# DVT-Volga-V2.net
KiCad netlist of a schematic drawn in Altium Designer
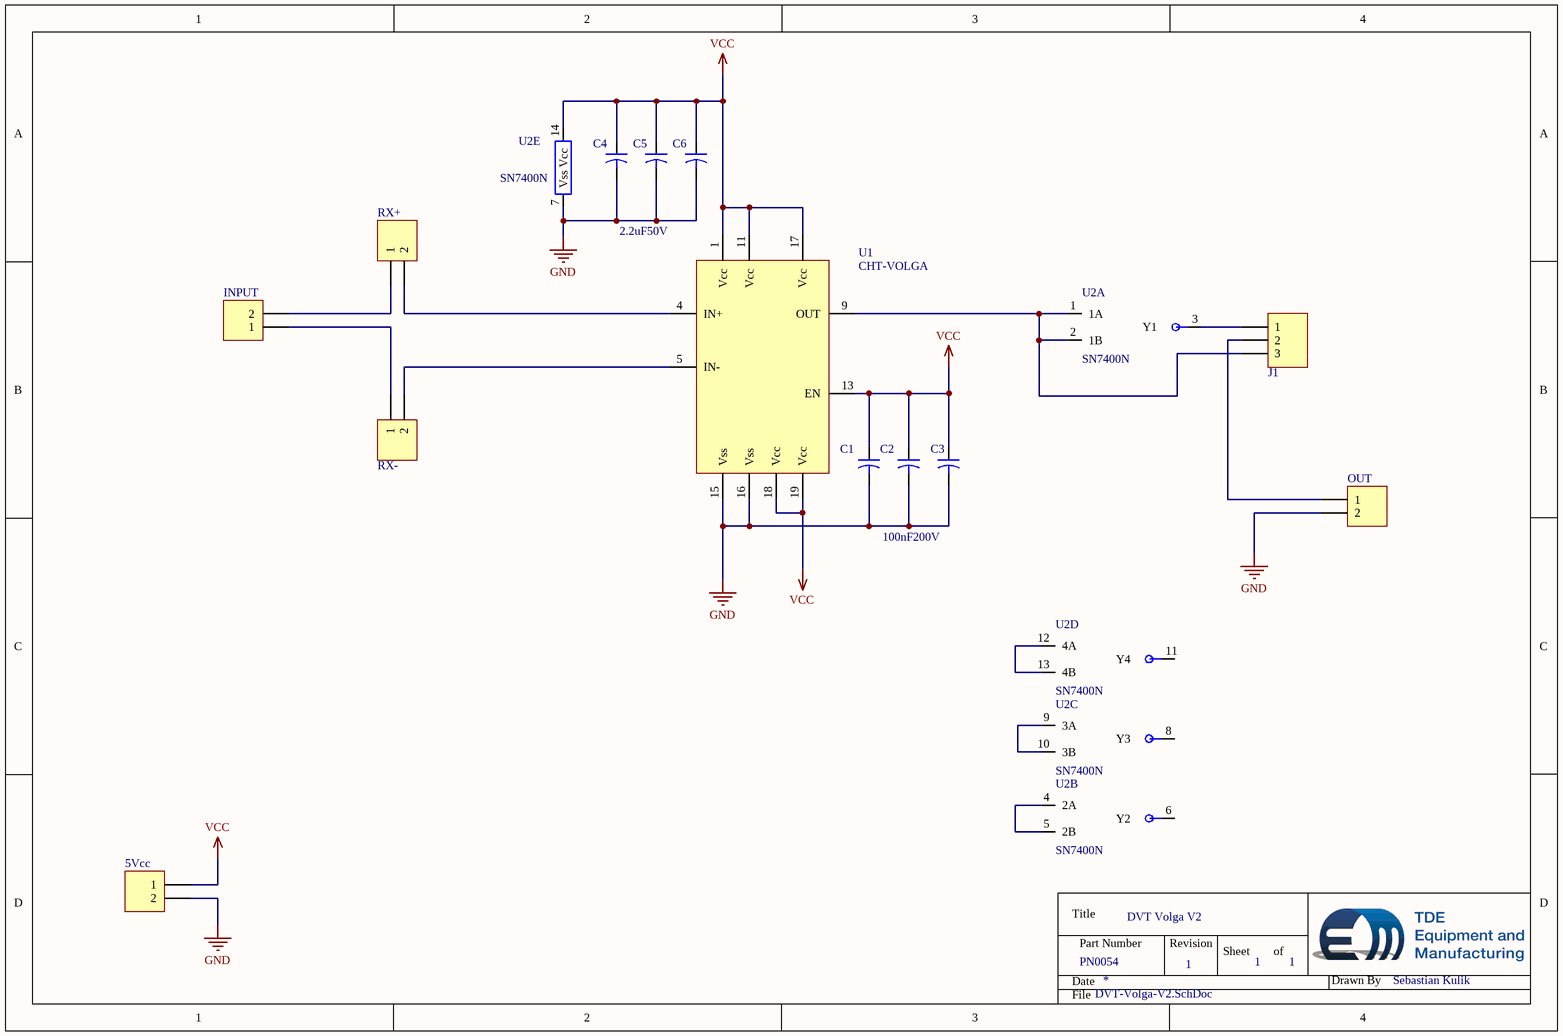
[diagram p0: DVT-Volga-V2.SchDoc]

(export (version "E")
  (design (tool "Eeschema 10.0.6"))
  (components
    (comp (ref "5Vcc")
      (value "PHOENIX_1715721")
      (footprint "Phoenix-2-5_08")
      (description "Phoenix, 2 pol, 5.08mm, 22A, 715721")
      (fields (field (name "MANUFACTURER") "Phoenix") (field (name "PUBLISHER") "Sebastian Kulik"))
      (libsource (lib "Connectors") (part "2Pol_1715721"))
    )
    (comp (ref "C1")
      (value "100nF200V")
      (footprint "Dummy-10mm")
      (description "Capacitor-Dummy-THT")
      (fields (field (name "PUBLISHER") "Sebastian Kulik"))
      (libsource (lib "Capacitors") (part "Capacitor-Dummy-THT"))
    )
    (comp (ref "C2")
      (value "Capacitor-Dummy-THT")
      (footprint "Dummy-10mm")
      (fields (field (name "PUBLISHER") "Sebastian Kulik"))
      (libsource (lib "Capacitors") (part "Capacitor-Dummy-THT"))
    )
    (comp (ref "C3")
      (value "Capacitor-Dummy-THT")
      (footprint "Dummy-10mm")
      (fields (field (name "PUBLISHER") "Sebastian Kulik"))
      (libsource (lib "Capacitors") (part "Capacitor-Dummy-THT"))
    )
    (comp (ref "C4")
      (value "Capacitor-Dummy-THT")
      (footprint "Dummy-10mm")
      (fields (field (name "PUBLISHER") "Sebastian Kulik"))
      (libsource (lib "Capacitors") (part "Capacitor-Dummy-THT"))
    )
    (comp (ref "C5")
      (value "Capacitor-Dummy-THT")
      (footprint "Dummy-10mm")
      (fields (field (name "PUBLISHER") "Sebastian Kulik"))
      (libsource (lib "Capacitors") (part "Capacitor-Dummy-THT"))
    )
    (comp (ref "C6")
      (value "2.2uF50V")
      (footprint "Dummy-10mm")
      (description "Capacitor-Dummy-THT")
      (fields (field (name "PUBLISHER") "Sebastian Kulik"))
      (libsource (lib "Capacitors") (part "Capacitor-Dummy-THT"))
    )
    (comp (ref "INPUT")
      (value "PHOENIX_1715721")
      (footprint "Phoenix-2-5_08")
      (description "Phoenix, 2 pol, 5.08mm, 22A, 715721")
      (fields (field (name "MANUFACTURER") "Phoenix") (field (name "PUBLISHER") "Sebastian Kulik"))
      (libsource (lib "") (part "2Pol_1715721_2"))
    )
    (comp (ref "J1")
      (value "Header-3")
      (footprint "HDR1X3")
      (description "Header-3-Pin")
      (fields (field (name "PUBLISHER") "Sebastian Kulik"))
      (libsource (lib "Connectors") (part "Header-3"))
    )
    (comp (ref "OUT")
      (value "PHOENIX_1715721")
      (footprint "Phoenix-2-5_08")
      (description "Phoenix, 2 pol, 5.08mm, 22A, 715721")
      (fields (field (name "MANUFACTURER") "Phoenix") (field (name "PUBLISHER") "Sebastian Kulik"))
      (libsource (lib "") (part "2Pol_1715721_1"))
    )
    (comp (ref "RX+")
      (value "PHOENIX_1715721")
      (footprint "HDR1X2")
      (description "Header, 2-Pin")
      (fields (field (name "PUBLISHER") "Sebastian Kulik"))
      (libsource (lib "") (part "Header-2_1"))
    )
    (comp (ref "RX-")
      (value "PHOENIX_1715721")
      (footprint "HDR1X2")
      (description "Header, 2-Pin")
      (fields (field (name "PUBLISHER") "Sebastian Kulik"))
      (libsource (lib "Connectors") (part "Header-2"))
    )
    (comp (ref "U1")
      (value "CHT-VOLGA")
      (footprint "TDFP16")
      (description "Comparator, Hi-Temp, 25MHz")
      (fields (field (name "MANUFACTURER") "CISSOID") (field (name "PUBLISHER") "Sebastian Kulik"))
      (libsource (lib "ICs") (part "CHT-VOLGA"))
    )
    (comp (ref "U2")
      (value "SN7400N")
      (footprint "DIP-14")
      (description "Quad NAND, TTL")
      (fields (field (name "MANUFACTURER") "TI") (field (name "PUBLISHER") "Sebastian Kulik"))
      (libsource (lib "ICs") (part "SN7400N"))
    )
  )
  (nets
    (net (code "1") (name "GND") (class "Default")
      (node (ref "5Vcc") (pin "2") (pinfunction "2_2") (pintype "passive"))
      (node (ref "C1") (pin "2") (pinfunction "2_2") (pintype "passive"))
      (node (ref "C2") (pin "2") (pinfunction "2_2") (pintype "passive"))
      (node (ref "C3") (pin "2") (pinfunction "2_2") (pintype "passive"))
      (node (ref "C4") (pin "2") (pinfunction "2_2") (pintype "passive"))
      (node (ref "C5") (pin "2") (pinfunction "2_2") (pintype "passive"))
      (node (ref "C6") (pin "2") (pinfunction "2_2") (pintype "passive"))
      (node (ref "OUT") (pin "2") (pinfunction "2_2") (pintype "passive"))
      (node (ref "U1") (pin "15") (pinfunction "Vss_15") (pintype "power_in"))
      (node (ref "U1") (pin "16") (pinfunction "Vss_16") (pintype "passive"))
      (node (ref "U2") (pin "7") (pinfunction "Vss_7") (pintype "passive"))
    )
    (net (code "2") (name "Net-(INPUT-Pad1)") (class "Default")
      (node (ref "INPUT") (pin "1") (pinfunction "1_1") (pintype "passive"))
      (node (ref "RX-") (pin "1") (pinfunction "1_1") (pintype "passive"))
    )
    (net (code "3") (name "Net-(INPUT-Pad2)") (class "Default")
      (node (ref "INPUT") (pin "2") (pinfunction "2_2") (pintype "passive"))
      (node (ref "RX+") (pin "1") (pinfunction "1_1") (pintype "passive"))
    )
    (net (code "4") (name "Net-(J1-Pad2)") (class "Default")
      (node (ref "J1") (pin "2") (pinfunction "2_2") (pintype "passive"))
      (node (ref "OUT") (pin "1") (pinfunction "1_1") (pintype "passive"))
    )
    (net (code "5") (name "Net-(U1-IN+)") (class "Default")
      (node (ref "RX+") (pin "2") (pinfunction "2_2") (pintype "passive"))
      (node (ref "U1") (pin "4") (pinfunction "IN+_4") (pintype "passive"))
    )
    (net (code "6") (name "Net-(U1-IN-)") (class "Default")
      (node (ref "RX-") (pin "2") (pinfunction "2_2") (pintype "passive"))
      (node (ref "U1") (pin "5") (pinfunction "IN-_5") (pintype "passive"))
    )
    (net (code "7") (name "Net-(U1-OUT)") (class "Default")
      (node (ref "J1") (pin "3") (pinfunction "3_3") (pintype "passive"))
      (node (ref "U1") (pin "9") (pinfunction "OUT_9") (pintype "power_in"))
      (node (ref "U2") (pin "1") (pinfunction "1A_1") (pintype "passive"))
      (node (ref "U2") (pin "2") (pinfunction "1B_2") (pintype "passive"))
    )
    (net (code "8") (name "Net-(U2A-Y1)") (class "Default")
      (node (ref "J1") (pin "1") (pinfunction "1_1") (pintype "passive"))
      (node (ref "U2") (pin "3") (pinfunction "Y1_3") (pintype "passive"))
    )
    (net (code "9") (name "Net-(U2B-2A)") (class "Default")
      (node (ref "U2") (pin "4") (pinfunction "2A_4") (pintype "passive"))
      (node (ref "U2") (pin "5") (pinfunction "2B_5") (pintype "passive"))
    )
    (net (code "10") (name "Net-(U2C-3A)") (class "Default")
      (node (ref "U2") (pin "10") (pinfunction "3B_10") (pintype "passive"))
      (node (ref "U2") (pin "9") (pinfunction "3A_9") (pintype "passive"))
    )
    (net (code "11") (name "Net-(U2D-4A)") (class "Default")
      (node (ref "U2") (pin "12") (pinfunction "4A_12") (pintype "passive"))
      (node (ref "U2") (pin "13") (pinfunction "4B_13") (pintype "passive"))
    )
    (net (code "12") (name "VCC") (class "Default")
      (node (ref "5Vcc") (pin "1") (pinfunction "1_1") (pintype "passive"))
      (node (ref "C1") (pin "1") (pinfunction "1_1") (pintype "passive"))
      (node (ref "C2") (pin "1") (pinfunction "1_1") (pintype "passive"))
      (node (ref "C3") (pin "1") (pinfunction "1_1") (pintype "passive"))
      (node (ref "C4") (pin "1") (pinfunction "1_1") (pintype "passive"))
      (node (ref "C5") (pin "1") (pinfunction "1_1") (pintype "passive"))
      (node (ref "C6") (pin "1") (pinfunction "1_1") (pintype "passive"))
      (node (ref "U1") (pin "1") (pinfunction "Vcc_1") (pintype "passive"))
      (node (ref "U1") (pin "11") (pinfunction "Vcc_11") (pintype "power_in"))
      (node (ref "U1") (pin "13") (pinfunction "EN_13") (pintype "passive"))
      (node (ref "U1") (pin "17") (pinfunction "Vcc_17") (pintype "passive"))
      (node (ref "U1") (pin "18") (pinfunction "Vcc_18") (pintype "power_in"))
      (node (ref "U1") (pin "19") (pinfunction "Vcc_19") (pintype "power_in"))
      (node (ref "U2") (pin "14") (pinfunction "Vcc_14") (pintype "passive"))
    )
    (net (code "13") (name "unconnected-(U2B-Y2-Pad6)") (class "Default")
      (node (ref "U2") (pin "6") (pinfunction "Y2_6") (pintype "passive"))
    )
    (net (code "14") (name "unconnected-(U2C-Y3-Pad8)") (class "Default")
      (node (ref "U2") (pin "8") (pinfunction "Y3_8") (pintype "passive"))
    )
    (net (code "15") (name "unconnected-(U2D-Y4-Pad11)") (class "Default")
      (node (ref "U2") (pin "11") (pinfunction "Y4_11") (pintype "passive"))
    )
  )
)
